# Schematic_board.net
KiCad netlist of a schematic drawn in EAGLE
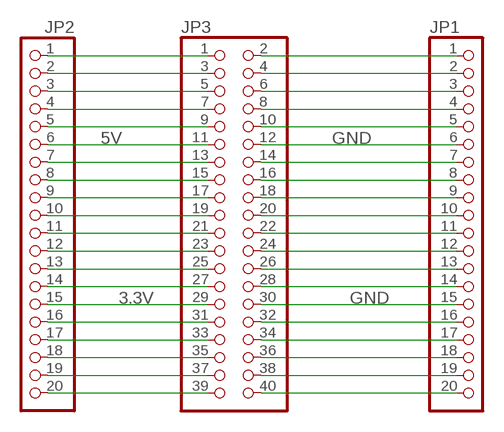
[diagram p0: schematic, sheet 1]

(export (version "E")
  (design (tool "Eeschema 10.0.6"))
  (components
    (comp (ref "JP1")
      (value "PINHD-1X20")
      (footprint "eagle-import:1X20")
      (libsource (lib "eagle-import") (part "PINHD-1X20"))
    )
    (comp (ref "JP2")
      (value "PINHD-1X20")
      (footprint "eagle-import:1X20")
      (libsource (lib "eagle-import") (part "PINHD-1X20"))
    )
    (comp (ref "JP3")
      (value "PINHD-2X20")
      (footprint "eagle-import:2X20")
      (libsource (lib "eagle-import") (part "PINHD-2X20"))
    )
  )
  (nets
    (net (code "1") (name "/3.3V") (class "Default")
      (node (ref "JP2") (pin "15") (pinfunction "15_15") (pintype "passive"))
      (node (ref "JP3") (pin "29") (pinfunction "29_29") (pintype "passive"))
    )
    (net (code "2") (name "/5V") (class "Default")
      (node (ref "JP2") (pin "6") (pinfunction "6_6") (pintype "passive"))
      (node (ref "JP3") (pin "11") (pinfunction "11_11") (pintype "passive"))
    )
    (net (code "3") (name "/GND") (class "Default")
      (node (ref "JP1") (pin "15") (pinfunction "15_15") (pintype "passive"))
      (node (ref "JP1") (pin "6") (pinfunction "6_6") (pintype "passive"))
      (node (ref "JP3") (pin "12") (pinfunction "12_12") (pintype "passive"))
      (node (ref "JP3") (pin "30") (pinfunction "30_30") (pintype "passive"))
    )
    (net (code "4") (name "Net-(JP1-Pad1)") (class "Default")
      (node (ref "JP1") (pin "1") (pinfunction "1_1") (pintype "passive"))
      (node (ref "JP3") (pin "2") (pinfunction "2_2") (pintype "passive"))
    )
    (net (code "5") (name "Net-(JP1-Pad2)") (class "Default")
      (node (ref "JP1") (pin "2") (pinfunction "2_2") (pintype "passive"))
      (node (ref "JP3") (pin "4") (pinfunction "4_4") (pintype "passive"))
    )
    (net (code "6") (name "Net-(JP1-Pad3)") (class "Default")
      (node (ref "JP1") (pin "3") (pinfunction "3_3") (pintype "passive"))
      (node (ref "JP3") (pin "6") (pinfunction "6_6") (pintype "passive"))
    )
    (net (code "7") (name "Net-(JP1-Pad4)") (class "Default")
      (node (ref "JP1") (pin "4") (pinfunction "4_4") (pintype "passive"))
      (node (ref "JP3") (pin "8") (pinfunction "8_8") (pintype "passive"))
    )
    (net (code "8") (name "Net-(JP1-Pad5)") (class "Default")
      (node (ref "JP1") (pin "5") (pinfunction "5_5") (pintype "passive"))
      (node (ref "JP3") (pin "10") (pinfunction "10_10") (pintype "passive"))
    )
    (net (code "9") (name "Net-(JP1-Pad7)") (class "Default")
      (node (ref "JP1") (pin "7") (pinfunction "7_7") (pintype "passive"))
      (node (ref "JP3") (pin "14") (pinfunction "14_14") (pintype "passive"))
    )
    (net (code "10") (name "Net-(JP1-Pad8)") (class "Default")
      (node (ref "JP1") (pin "8") (pinfunction "8_8") (pintype "passive"))
      (node (ref "JP3") (pin "16") (pinfunction "16_16") (pintype "passive"))
    )
    (net (code "11") (name "Net-(JP1-Pad9)") (class "Default")
      (node (ref "JP1") (pin "9") (pinfunction "9_9") (pintype "passive"))
      (node (ref "JP3") (pin "18") (pinfunction "18_18") (pintype "passive"))
    )
    (net (code "12") (name "Net-(JP1-Pad10)") (class "Default")
      (node (ref "JP1") (pin "10") (pinfunction "10_10") (pintype "passive"))
      (node (ref "JP3") (pin "20") (pinfunction "20_20") (pintype "passive"))
    )
    (net (code "13") (name "Net-(JP1-Pad11)") (class "Default")
      (node (ref "JP1") (pin "11") (pinfunction "11_11") (pintype "passive"))
      (node (ref "JP3") (pin "22") (pinfunction "22_22") (pintype "passive"))
    )
    (net (code "14") (name "Net-(JP1-Pad12)") (class "Default")
      (node (ref "JP1") (pin "12") (pinfunction "12_12") (pintype "passive"))
      (node (ref "JP3") (pin "24") (pinfunction "24_24") (pintype "passive"))
    )
    (net (code "15") (name "Net-(JP1-Pad13)") (class "Default")
      (node (ref "JP1") (pin "13") (pinfunction "13_13") (pintype "passive"))
      (node (ref "JP3") (pin "26") (pinfunction "26_26") (pintype "passive"))
    )
    (net (code "16") (name "Net-(JP1-Pad14)") (class "Default")
      (node (ref "JP1") (pin "14") (pinfunction "14_14") (pintype "passive"))
      (node (ref "JP3") (pin "28") (pinfunction "28_28") (pintype "passive"))
    )
    (net (code "17") (name "Net-(JP1-Pad16)") (class "Default")
      (node (ref "JP1") (pin "16") (pinfunction "16_16") (pintype "passive"))
      (node (ref "JP3") (pin "32") (pinfunction "32_32") (pintype "passive"))
    )
    (net (code "18") (name "Net-(JP1-Pad17)") (class "Default")
      (node (ref "JP1") (pin "17") (pinfunction "17_17") (pintype "passive"))
      (node (ref "JP3") (pin "34") (pinfunction "34_34") (pintype "passive"))
    )
    (net (code "19") (name "Net-(JP1-Pad18)") (class "Default")
      (node (ref "JP1") (pin "18") (pinfunction "18_18") (pintype "passive"))
      (node (ref "JP3") (pin "36") (pinfunction "36_36") (pintype "passive"))
    )
    (net (code "20") (name "Net-(JP1-Pad19)") (class "Default")
      (node (ref "JP1") (pin "19") (pinfunction "19_19") (pintype "passive"))
      (node (ref "JP3") (pin "38") (pinfunction "38_38") (pintype "passive"))
    )
    (net (code "21") (name "Net-(JP1-Pad20)") (class "Default")
      (node (ref "JP1") (pin "20") (pinfunction "20_20") (pintype "passive"))
      (node (ref "JP3") (pin "40") (pinfunction "40_40") (pintype "passive"))
    )
    (net (code "22") (name "Net-(JP2-Pad1)") (class "Default")
      (node (ref "JP2") (pin "1") (pinfunction "1_1") (pintype "passive"))
      (node (ref "JP3") (pin "1") (pinfunction "1_1") (pintype "passive"))
    )
    (net (code "23") (name "Net-(JP2-Pad2)") (class "Default")
      (node (ref "JP2") (pin "2") (pinfunction "2_2") (pintype "passive"))
      (node (ref "JP3") (pin "3") (pinfunction "3_3") (pintype "passive"))
    )
    (net (code "24") (name "Net-(JP2-Pad3)") (class "Default")
      (node (ref "JP2") (pin "3") (pinfunction "3_3") (pintype "passive"))
      (node (ref "JP3") (pin "5") (pinfunction "5_5") (pintype "passive"))
    )
    (net (code "25") (name "Net-(JP2-Pad4)") (class "Default")
      (node (ref "JP2") (pin "4") (pinfunction "4_4") (pintype "passive"))
      (node (ref "JP3") (pin "7") (pinfunction "7_7") (pintype "passive"))
    )
    (net (code "26") (name "Net-(JP2-Pad5)") (class "Default")
      (node (ref "JP2") (pin "5") (pinfunction "5_5") (pintype "passive"))
      (node (ref "JP3") (pin "9") (pinfunction "9_9") (pintype "passive"))
    )
    (net (code "27") (name "Net-(JP2-Pad7)") (class "Default")
      (node (ref "JP2") (pin "7") (pinfunction "7_7") (pintype "passive"))
      (node (ref "JP3") (pin "13") (pinfunction "13_13") (pintype "passive"))
    )
    (net (code "28") (name "Net-(JP2-Pad8)") (class "Default")
      (node (ref "JP2") (pin "8") (pinfunction "8_8") (pintype "passive"))
      (node (ref "JP3") (pin "15") (pinfunction "15_15") (pintype "passive"))
    )
    (net (code "29") (name "Net-(JP2-Pad9)") (class "Default")
      (node (ref "JP2") (pin "9") (pinfunction "9_9") (pintype "passive"))
      (node (ref "JP3") (pin "17") (pinfunction "17_17") (pintype "passive"))
    )
    (net (code "30") (name "Net-(JP2-Pad10)") (class "Default")
      (node (ref "JP2") (pin "10") (pinfunction "10_10") (pintype "passive"))
      (node (ref "JP3") (pin "19") (pinfunction "19_19") (pintype "passive"))
    )
    (net (code "31") (name "Net-(JP2-Pad11)") (class "Default")
      (node (ref "JP2") (pin "11") (pinfunction "11_11") (pintype "passive"))
      (node (ref "JP3") (pin "21") (pinfunction "21_21") (pintype "passive"))
    )
    (net (code "32") (name "Net-(JP2-Pad12)") (class "Default")
      (node (ref "JP2") (pin "12") (pinfunction "12_12") (pintype "passive"))
      (node (ref "JP3") (pin "23") (pinfunction "23_23") (pintype "passive"))
    )
    (net (code "33") (name "Net-(JP2-Pad13)") (class "Default")
      (node (ref "JP2") (pin "13") (pinfunction "13_13") (pintype "passive"))
      (node (ref "JP3") (pin "25") (pinfunction "25_25") (pintype "passive"))
    )
    (net (code "34") (name "Net-(JP2-Pad14)") (class "Default")
      (node (ref "JP2") (pin "14") (pinfunction "14_14") (pintype "passive"))
      (node (ref "JP3") (pin "27") (pinfunction "27_27") (pintype "passive"))
    )
    (net (code "35") (name "Net-(JP2-Pad16)") (class "Default")
      (node (ref "JP2") (pin "16") (pinfunction "16_16") (pintype "passive"))
      (node (ref "JP3") (pin "31") (pinfunction "31_31") (pintype "passive"))
    )
    (net (code "36") (name "Net-(JP2-Pad17)") (class "Default")
      (node (ref "JP2") (pin "17") (pinfunction "17_17") (pintype "passive"))
      (node (ref "JP3") (pin "33") (pinfunction "33_33") (pintype "passive"))
    )
    (net (code "37") (name "Net-(JP2-Pad18)") (class "Default")
      (node (ref "JP2") (pin "18") (pinfunction "18_18") (pintype "passive"))
      (node (ref "JP3") (pin "35") (pinfunction "35_35") (pintype "passive"))
    )
    (net (code "38") (name "Net-(JP2-Pad19)") (class "Default")
      (node (ref "JP2") (pin "19") (pinfunction "19_19") (pintype "passive"))
      (node (ref "JP3") (pin "37") (pinfunction "37_37") (pintype "passive"))
    )
    (net (code "39") (name "Net-(JP2-Pad20)") (class "Default")
      (node (ref "JP2") (pin "20") (pinfunction "20_20") (pintype "passive"))
      (node (ref "JP3") (pin "39") (pinfunction "39_39") (pintype "passive"))
    )
  )
)
